# ESPF.net
KiCad netlist of a schematic drawn in EAGLE
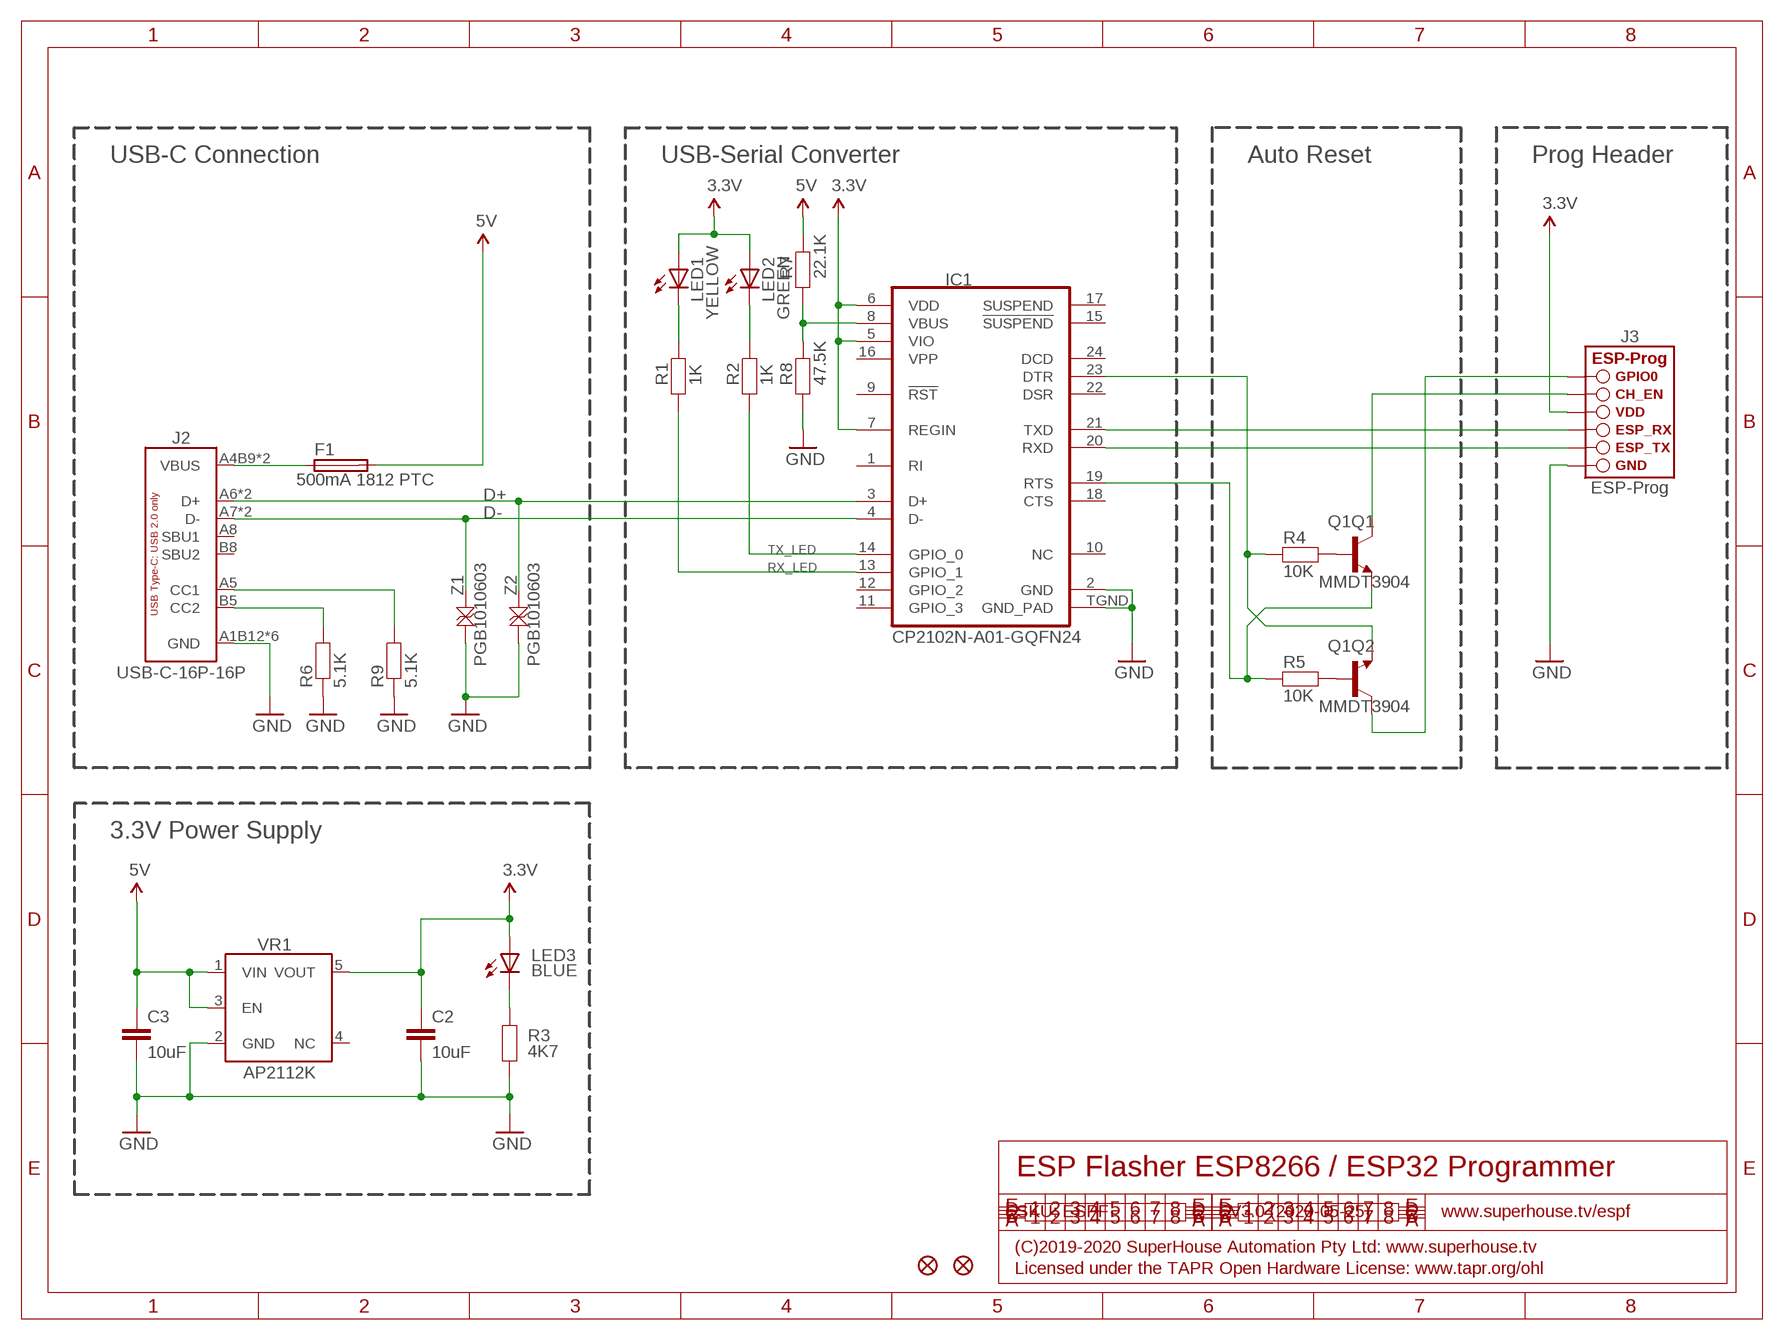
[diagram p0: schematic, sheet 1]

(export (version "E")
  (design (tool "Eeschema 10.0.6"))
  (components
    (comp (ref "C2")
      (value "10uF")
      (footprint "eagle-import:C0805")
      (libsource (lib "eagle-import") (part "CAP0805"))
    )
    (comp (ref "C3")
      (value "10uF")
      (footprint "eagle-import:C0805")
      (libsource (lib "eagle-import") (part "CAP0805"))
    )
    (comp (ref "F1")
      (value "500mA 1812 PTC")
      (footprint "eagle-import:1812")
      (libsource (lib "eagle-import") (part "PTC050"))
    )
    (comp (ref "FID1")
      (value "FIDUCIAL1X2.5")
      (footprint "eagle-import:FIDUCIAL-1X2.5")
      (libsource (lib "eagle-import") (part "FIDUCIAL1X2.5"))
    )
    (comp (ref "FID2")
      (value "FIDUCIAL1X2.5")
      (footprint "eagle-import:FIDUCIAL-1X2.5")
      (libsource (lib "eagle-import") (part "FIDUCIAL1X2.5"))
    )
    (comp (ref "IC1")
      (value "CP2102N-A01-GQFN24")
      (footprint "eagle-import:QFN-24")
      (libsource (lib "eagle-import") (part "CP2104"))
    )
    (comp (ref "J2")
      (value "USB-C-16P-16P")
      (footprint "eagle-import:USB-C-16P")
      (libsource (lib "eagle-import") (part "USB-C-16P-16P"))
    )
    (comp (ref "J3")
      (value "ESP-PROG-1X6-2.54-PINS-RA")
      (footprint "eagle-import:1X6-2.54-PINS-RA")
      (libsource (lib "eagle-import") (part "ESP-PROG-1X6-2.54-PINS-RA"))
    )
    (comp (ref "LED1")
      (value "YELLOW")
      (footprint "eagle-import:LED-0603")
      (libsource (lib "eagle-import") (part "LED0603"))
    )
    (comp (ref "LED2")
      (value "GREEN")
      (footprint "eagle-import:LED-0603")
      (libsource (lib "eagle-import") (part "LED0603"))
    )
    (comp (ref "LED3")
      (value "BLUE")
      (footprint "eagle-import:LED-0603")
      (libsource (lib "eagle-import") (part "LED0603"))
    )
    (comp (ref "Q1")
      (value "MMDT3904")
      (footprint "eagle-import:SOT-363")
      (libsource (lib "eagle-import") (part "TRANS_NPN_DUAL-MMDT3904"))
    )
    (comp (ref "R1")
      (value "1K")
      (footprint "eagle-import:R0603")
      (libsource (lib "eagle-import") (part "RESISTOR0603"))
    )
    (comp (ref "R2")
      (value "1K")
      (footprint "eagle-import:R0603")
      (libsource (lib "eagle-import") (part "RESISTOR0603"))
    )
    (comp (ref "R3")
      (value "4K7")
      (footprint "eagle-import:R0603")
      (libsource (lib "eagle-import") (part "RESISTOR0603"))
    )
    (comp (ref "R4")
      (value "10K")
      (footprint "eagle-import:R0603")
      (libsource (lib "eagle-import") (part "RESISTOR0603"))
    )
    (comp (ref "R5")
      (value "10K")
      (footprint "eagle-import:R0603")
      (libsource (lib "eagle-import") (part "RESISTOR0603"))
    )
    (comp (ref "R6")
      (value "5.1K")
      (footprint "eagle-import:R0603")
      (libsource (lib "eagle-import") (part "RESISTOR0603"))
    )
    (comp (ref "R7")
      (value "22.1K")
      (footprint "eagle-import:R0603")
      (libsource (lib "eagle-import") (part "RESISTOR0603"))
    )
    (comp (ref "R8")
      (value "47.5K")
      (footprint "eagle-import:R0603")
      (libsource (lib "eagle-import") (part "RESISTOR0603"))
    )
    (comp (ref "R9")
      (value "5.1K")
      (footprint "eagle-import:R0603")
      (libsource (lib "eagle-import") (part "RESISTOR0603"))
    )
    (comp (ref "VR1")
      (value "AP2112KSOT25")
      (footprint "eagle-import:SOT23-5")
      (libsource (lib "eagle-import") (part "AP2112KSOT25"))
    )
    (comp (ref "Z1")
      (value "PGB1010603")
      (footprint "eagle-import:TVS0603")
      (libsource (lib "eagle-import") (part "TVS0603"))
    )
    (comp (ref "Z2")
      (value "PGB1010603")
      (footprint "eagle-import:TVS0603")
      (libsource (lib "eagle-import") (part "TVS0603"))
    )
  )
  (nets
    (net (code "1") (name "/D+") (class "Default")
      (node (ref "IC1") (pin "3") (pinfunction "D+_3") (pintype "bidirectional"))
      (node (ref "J2") (pin "A6") (pinfunction "D+_A6") (pintype "bidirectional"))
      (node (ref "J2") (pin "B6") (pinfunction "D+_B6") (pintype "bidirectional"))
      (node (ref "Z2") (pin "2") (pinfunction "2_2") (pintype "passive"))
    )
    (net (code "2") (name "/D-") (class "Default")
      (node (ref "IC1") (pin "4") (pinfunction "D-_4") (pintype "bidirectional"))
      (node (ref "J2") (pin "A7") (pinfunction "D-_A7") (pintype "bidirectional"))
      (node (ref "J2") (pin "B7") (pinfunction "D-_B7") (pintype "bidirectional"))
      (node (ref "Z1") (pin "2") (pinfunction "2_2") (pintype "passive"))
    )
    (net (code "3") (name "/RX_LED") (class "Default")
      (node (ref "IC1") (pin "13") (pinfunction "GPIO_1_13") (pintype "bidirectional"))
      (node (ref "R1") (pin "1") (pinfunction "1_1") (pintype "passive"))
    )
    (net (code "4") (name "/TX_LED") (class "Default")
      (node (ref "IC1") (pin "14") (pinfunction "GPIO_0_14") (pintype "bidirectional"))
      (node (ref "R2") (pin "1") (pinfunction "1_1") (pintype "passive"))
    )
    (net (code "5") (name "3.3V") (class "Default")
      (node (ref "C2") (pin "1") (pinfunction "1_1") (pintype "passive"))
      (node (ref "IC1") (pin "5") (pinfunction "VIO_5") (pintype "bidirectional"))
      (node (ref "IC1") (pin "6") (pinfunction "VDD_6") (pintype "power_in"))
      (node (ref "IC1") (pin "7") (pinfunction "REGIN_7") (pintype "power_in"))
      (node (ref "J3") (pin "4") (pinfunction "VDD_4") (pintype "passive"))
      (node (ref "LED1") (pin "A") (pinfunction "A_A") (pintype "passive"))
      (node (ref "LED2") (pin "A") (pinfunction "A_A") (pintype "passive"))
      (node (ref "LED3") (pin "A") (pinfunction "A_A") (pintype "passive"))
      (node (ref "VR1") (pin "5") (pinfunction "VOUT_5") (pintype "bidirectional"))
    )
    (net (code "6") (name "5V") (class "Default")
      (node (ref "C3") (pin "1") (pinfunction "1_1") (pintype "passive"))
      (node (ref "F1") (pin "2") (pinfunction "2_2") (pintype "passive"))
      (node (ref "R7") (pin "2") (pinfunction "2_2") (pintype "passive"))
      (node (ref "VR1") (pin "1") (pinfunction "VIN_1") (pintype "bidirectional"))
      (node (ref "VR1") (pin "3") (pinfunction "EN_3") (pintype "bidirectional"))
    )
    (net (code "7") (name "GND") (class "Default")
      (node (ref "C2") (pin "2") (pinfunction "2_2") (pintype "passive"))
      (node (ref "C3") (pin "2") (pinfunction "2_2") (pintype "passive"))
      (node (ref "IC1") (pin "2") (pinfunction "GND_2") (pintype "power_in"))
      (node (ref "IC1") (pin "TGND") (pinfunction "GND_PAD_TGND") (pintype "power_in"))
      (node (ref "J2") (pin "A12B1") (pinfunction "GND_A12B1") (pintype "power_in"))
      (node (ref "J2") (pin "A1B12") (pinfunction "GND_A1B12") (pintype "power_in"))
      (node (ref "J2") (pin "FIX1") (pinfunction "GND_FIX1") (pintype "power_in"))
      (node (ref "J2") (pin "FIX2") (pinfunction "GND_FIX2") (pintype "power_in"))
      (node (ref "J2") (pin "FIX3") (pinfunction "GND_FIX3") (pintype "power_in"))
      (node (ref "J2") (pin "FIX4") (pinfunction "GND_FIX4") (pintype "power_in"))
      (node (ref "J3") (pin "1") (pinfunction "GND_1") (pintype "passive"))
      (node (ref "R3") (pin "1") (pinfunction "1_1") (pintype "passive"))
      (node (ref "R6") (pin "1") (pinfunction "1_1") (pintype "passive"))
      (node (ref "R8") (pin "1") (pinfunction "1_1") (pintype "passive"))
      (node (ref "R9") (pin "1") (pinfunction "1_1") (pintype "passive"))
      (node (ref "VR1") (pin "2") (pinfunction "GND_2") (pintype "bidirectional"))
      (node (ref "Z1") (pin "1") (pinfunction "1_1") (pintype "passive"))
      (node (ref "Z2") (pin "1") (pinfunction "1_1") (pintype "passive"))
    )
    (net (code "8") (name "Net-(F1-Pad1)") (class "Default")
      (node (ref "F1") (pin "1") (pinfunction "1_1") (pintype "passive"))
      (node (ref "J2") (pin "A4B9") (pinfunction "VBUS_A4B9") (pintype "power_in"))
      (node (ref "J2") (pin "A9B4") (pinfunction "VBUS_A9B4") (pintype "power_in"))
    )
    (net (code "9") (name "Net-(IC1-DTR)") (class "Default")
      (node (ref "IC1") (pin "23") (pinfunction "DTR_23") (pintype "output"))
      (node (ref "Q1") (pin "1") (pinfunction "E_1") (pintype "passive"))
      (node (ref "R4") (pin "1") (pinfunction "1_1") (pintype "passive"))
    )
    (net (code "10") (name "Net-(IC1-RTS)") (class "Default")
      (node (ref "IC1") (pin "19") (pinfunction "RTS_19") (pintype "output"))
      (node (ref "Q1") (pin "4") (pinfunction "E_4") (pintype "passive"))
      (node (ref "R5") (pin "1") (pinfunction "1_1") (pintype "passive"))
    )
    (net (code "11") (name "Net-(IC1-RXD)") (class "Default")
      (node (ref "IC1") (pin "20") (pinfunction "RXD_20") (pintype "input"))
      (node (ref "J3") (pin "2") (pinfunction "ESP_TX_2") (pintype "passive"))
    )
    (net (code "12") (name "Net-(IC1-TXD)") (class "Default")
      (node (ref "IC1") (pin "21") (pinfunction "TXD_21") (pintype "output"))
      (node (ref "J3") (pin "3") (pinfunction "ESP_RX_3") (pintype "passive"))
    )
    (net (code "13") (name "Net-(IC1-VBUS)") (class "Default")
      (node (ref "IC1") (pin "8") (pinfunction "VBUS_8") (pintype "bidirectional"))
      (node (ref "R7") (pin "1") (pinfunction "1_1") (pintype "passive"))
      (node (ref "R8") (pin "2") (pinfunction "2_2") (pintype "passive"))
    )
    (net (code "14") (name "Net-(J2-CC1)") (class "Default")
      (node (ref "J2") (pin "A5") (pinfunction "CC1_A5") (pintype "bidirectional"))
      (node (ref "R9") (pin "2") (pinfunction "2_2") (pintype "passive"))
    )
    (net (code "15") (name "Net-(J2-CC2)") (class "Default")
      (node (ref "J2") (pin "B5") (pinfunction "CC2_B5") (pintype "bidirectional"))
      (node (ref "R6") (pin "2") (pinfunction "2_2") (pintype "passive"))
    )
    (net (code "16") (name "Net-(J3-CH_EN)") (class "Default")
      (node (ref "J3") (pin "5") (pinfunction "CH_EN_5") (pintype "passive"))
      (node (ref "Q1") (pin "3") (pinfunction "C_3") (pintype "passive"))
    )
    (net (code "17") (name "Net-(J3-GPIO0)") (class "Default")
      (node (ref "J3") (pin "6") (pinfunction "GPIO0_6") (pintype "passive"))
      (node (ref "Q1") (pin "6") (pinfunction "C_6") (pintype "passive"))
    )
    (net (code "18") (name "Net-(LED1-PadC)") (class "Default")
      (node (ref "LED1") (pin "C") (pinfunction "C_C") (pintype "passive"))
      (node (ref "R1") (pin "2") (pinfunction "2_2") (pintype "passive"))
    )
    (net (code "19") (name "Net-(LED2-PadC)") (class "Default")
      (node (ref "LED2") (pin "C") (pinfunction "C_C") (pintype "passive"))
      (node (ref "R2") (pin "2") (pinfunction "2_2") (pintype "passive"))
    )
    (net (code "20") (name "Net-(LED3-PadC)") (class "Default")
      (node (ref "LED3") (pin "C") (pinfunction "C_C") (pintype "passive"))
      (node (ref "R3") (pin "2") (pinfunction "2_2") (pintype "passive"))
    )
    (net (code "21") (name "Net-(Q1A-B)") (class "Default")
      (node (ref "Q1") (pin "5") (pinfunction "B_5") (pintype "passive"))
      (node (ref "R4") (pin "2") (pinfunction "2_2") (pintype "passive"))
    )
    (net (code "22") (name "Net-(Q1B-B)") (class "Default")
      (node (ref "Q1") (pin "2") (pinfunction "B_2") (pintype "passive"))
      (node (ref "R5") (pin "2") (pinfunction "2_2") (pintype "passive"))
    )
    (net (code "23") (name "unconnected-(IC1-CTS-Pad18)") (class "Default")
      (node (ref "IC1") (pin "18") (pinfunction "CTS_18") (pintype "input"))
    )
    (net (code "24") (name "unconnected-(IC1-DCD-Pad24)") (class "Default")
      (node (ref "IC1") (pin "24") (pinfunction "DCD_24") (pintype "input"))
    )
    (net (code "25") (name "unconnected-(IC1-DSR-Pad22)") (class "Default")
      (node (ref "IC1") (pin "22") (pinfunction "DSR_22") (pintype "input"))
    )
    (net (code "26") (name "unconnected-(IC1-GPIO_2-Pad12)") (class "Default")
      (node (ref "IC1") (pin "12") (pinfunction "GPIO_2_12") (pintype "bidirectional"))
    )
    (net (code "27") (name "unconnected-(IC1-GPIO_3-Pad11)") (class "Default")
      (node (ref "IC1") (pin "11") (pinfunction "GPIO_3_11") (pintype "bidirectional"))
    )
    (net (code "28") (name "unconnected-(IC1-NC-Pad10)") (class "Default")
      (node (ref "IC1") (pin "10") (pinfunction "NC_10") (pintype "input"))
    )
    (net (code "29") (name "unconnected-(IC1-RI-Pad1)") (class "Default")
      (node (ref "IC1") (pin "1") (pinfunction "RI_1") (pintype "input"))
    )
    (net (code "30") (name "unconnected-(IC1-SUSPEND-Pad17)") (class "Default")
      (node (ref "IC1") (pin "17") (pinfunction "SUSPEND_17") (pintype "output"))
    )
    (net (code "31") (name "unconnected-(IC1-VPP-Pad16)") (class "Default")
      (node (ref "IC1") (pin "16") (pinfunction "VPP_16") (pintype "bidirectional"))
    )
    (net (code "32") (name "unconnected-(IC1-~{RST}-Pad9)") (class "Default")
      (node (ref "IC1") (pin "9") (pinfunction "~{RST}_9") (pintype "bidirectional"))
    )
    (net (code "33") (name "unconnected-(IC1-~{SUSPEND}-Pad15)") (class "Default")
      (node (ref "IC1") (pin "15") (pinfunction "~{SUSPEND}_15") (pintype "output"))
    )
    (net (code "34") (name "unconnected-(J2-SBU1-PadA8)") (class "Default")
      (node (ref "J2") (pin "A8") (pinfunction "SBU1_A8") (pintype "bidirectional"))
    )
    (net (code "35") (name "unconnected-(J2-SBU2-PadB8)") (class "Default")
      (node (ref "J2") (pin "B8") (pinfunction "SBU2_B8") (pintype "bidirectional"))
    )
    (net (code "36") (name "unconnected-(VR1-NC-Pad4)") (class "Default")
      (node (ref "VR1") (pin "4") (pinfunction "NC_4") (pintype "bidirectional"))
    )
  )
)
